# Walrus_Main.net
KiCad netlist of a schematic drawn in Altium Designer
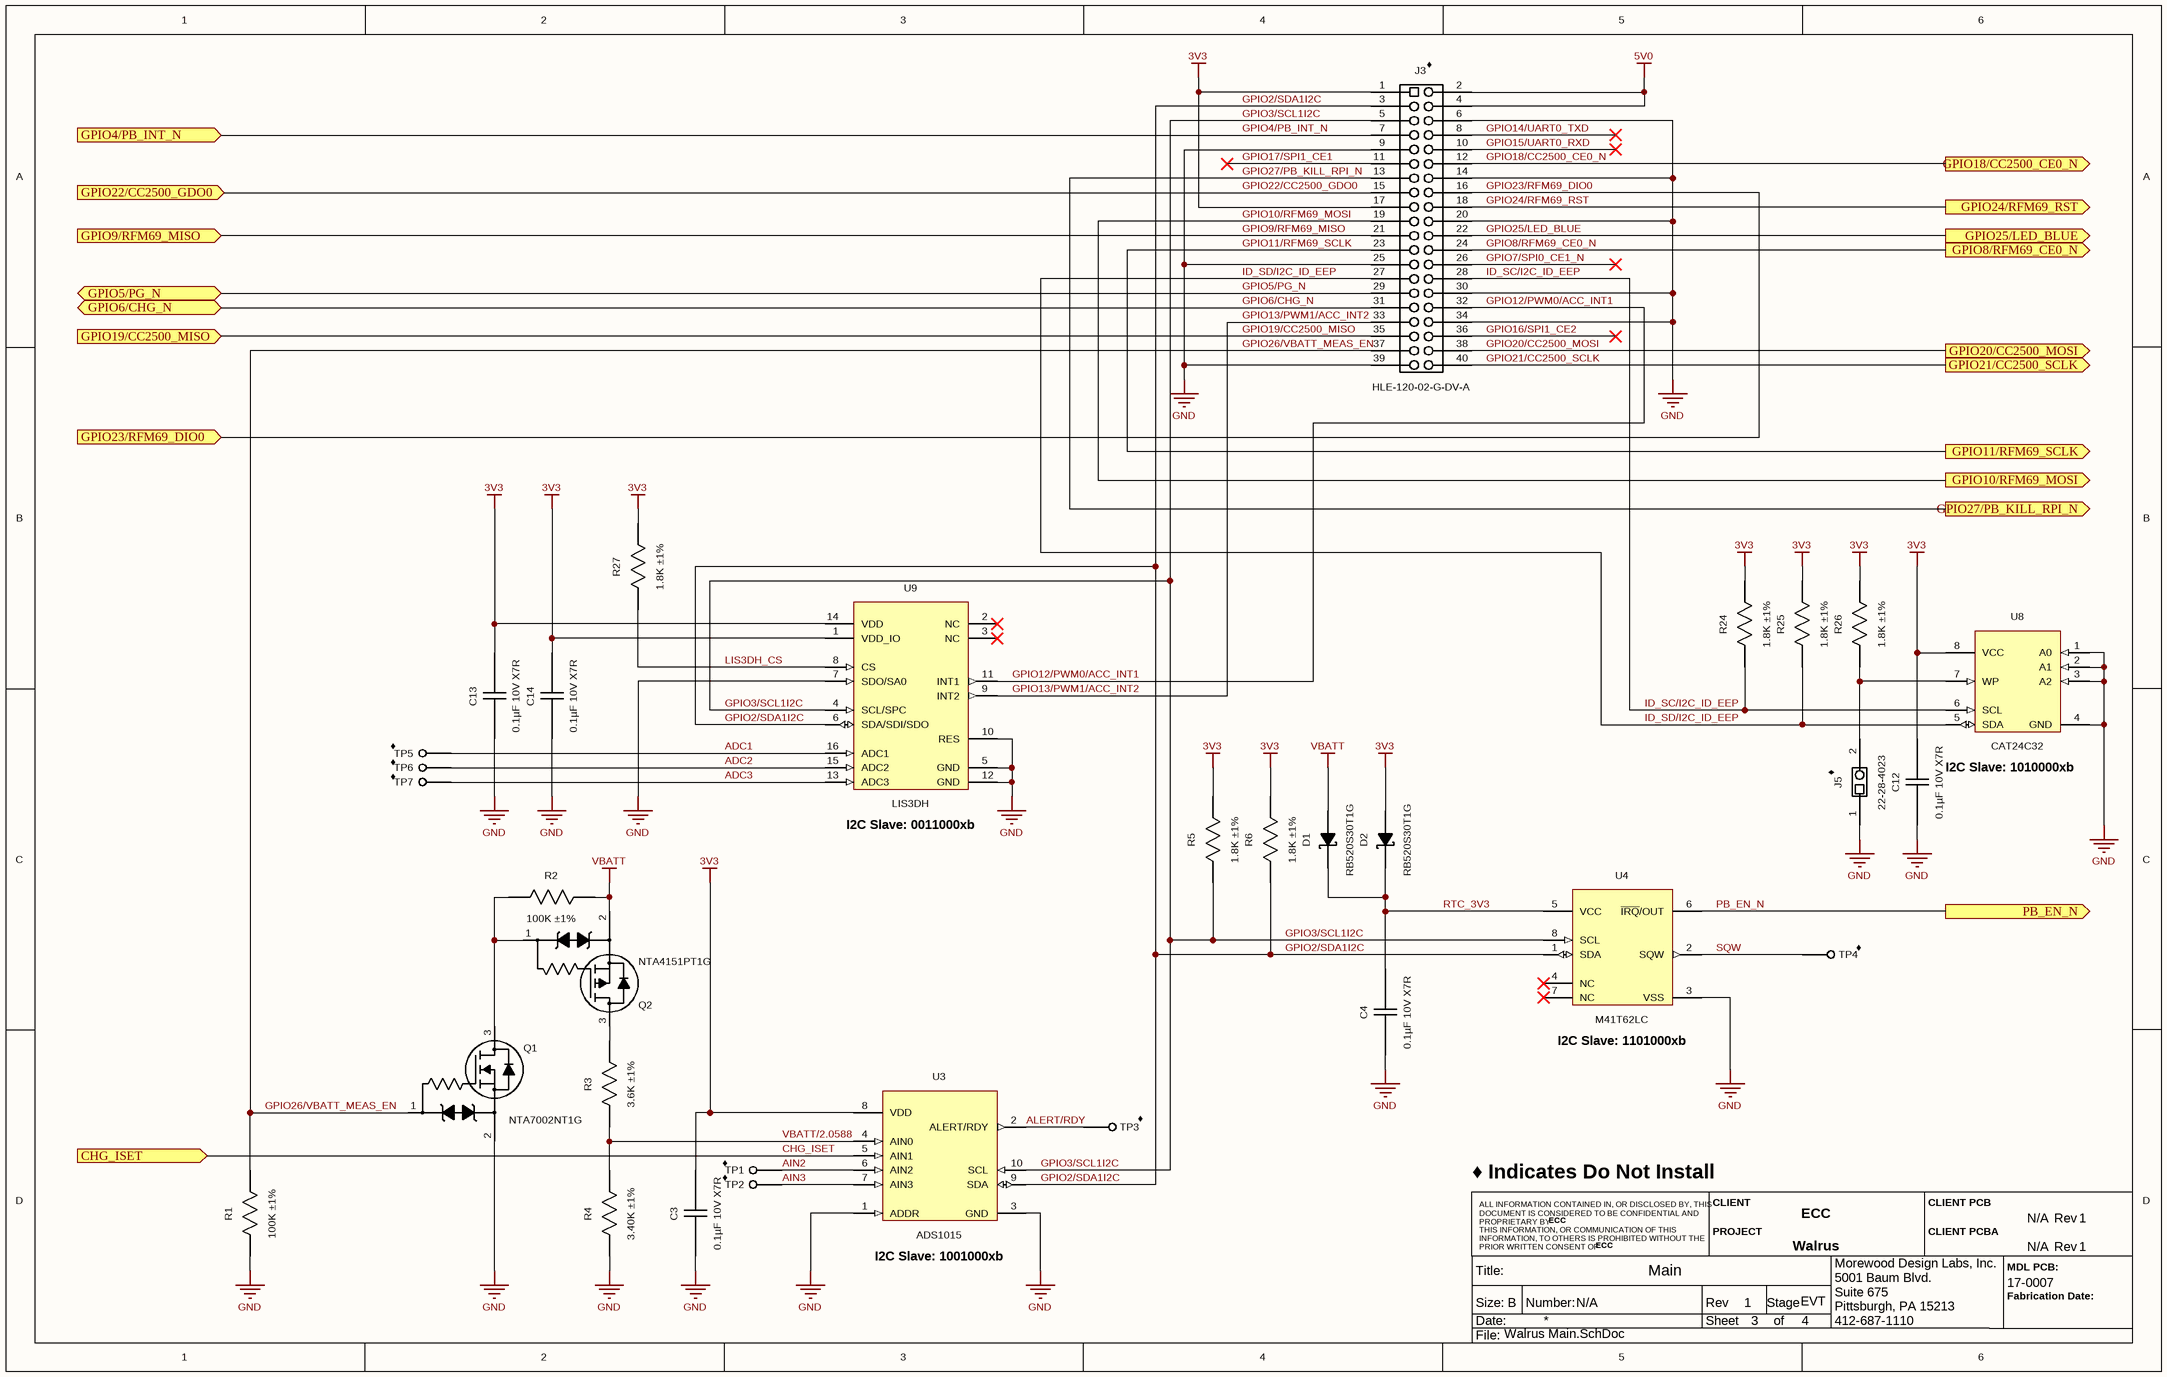
[diagram p0: Walrus Main.SchDoc]

(export (version "E")
  (design (tool "Eeschema 10.0.6"))
  (components
    (comp (ref "C3")
      (value "0.1µF 10V X7R")
      (footprint "CAPC1005X60L(0402_FLEXTRONICS)")
      (description "Ceramic Chip Capacitor")
      (fields
        (field (name "MDLPARTNUMBER") "CAP_000208")
        (field (name "TOLERANCE") "±10%")
        (field (name "CREATOR") "R. Casciola")
      )
      (libsource (lib "Morewood Labs") (part "Capacitor 1"))
    )
    (comp (ref "C4")
      (value "0.1µF 10V X7R")
      (footprint "CAPC1005X60L(0402_FLEXTRONICS)")
      (description "Ceramic Chip Capacitor")
      (fields
        (field (name "MDLPARTNUMBER") "CAP_000208")
        (field (name "TOLERANCE") "±10%")
        (field (name "CREATOR") "R. Casciola")
      )
      (libsource (lib "Morewood Labs") (part "Capacitor 1"))
    )
    (comp (ref "C12")
      (value "0.1µF 10V X7R")
      (footprint "CAPC1005X60L(0402_FLEXTRONICS)")
      (description "Ceramic Chip Capacitor")
      (fields
        (field (name "MDLPARTNUMBER") "CAP_000208")
        (field (name "TOLERANCE") "±10%")
        (field (name "CREATOR") "R. Casciola")
      )
      (libsource (lib "Morewood Labs") (part "Capacitor 1"))
    )
    (comp (ref "C13")
      (value "0.1µF 10V X7R")
      (footprint "CAPC1005X60L(0402_FLEXTRONICS)")
      (description "Ceramic Chip Capacitor")
      (fields
        (field (name "MDLPARTNUMBER") "CAP_000208")
        (field (name "TOLERANCE") "±10%")
        (field (name "CREATOR") "R. Casciola")
      )
      (libsource (lib "Morewood Labs") (part "Capacitor 1"))
    )
    (comp (ref "C14")
      (value "0.1µF 10V X7R")
      (footprint "CAPC1005X60L(0402_FLEXTRONICS)")
      (description "Ceramic Chip Capacitor")
      (fields
        (field (name "MDLPARTNUMBER") "CAP_000208")
        (field (name "TOLERANCE") "±10%")
        (field (name "CREATOR") "R. Casciola")
      )
      (libsource (lib "Morewood Labs") (part "Capacitor 1"))
    )
    (comp (ref "D1")
      (value "RB520S30T1G")
      (footprint "SODFL1608X70L(SOD-523)")
      (description "Schottky Barrier Diode")
      (fields (field (name "MDLPARTNUMBER") "DIOD_000001") (field (name "CREATOR") "R. Casciola"))
      (libsource (lib "Morewood Labs") (part "Diode 3"))
    )
    (comp (ref "D2")
      (value "RB520S30T1G")
      (footprint "SODFL1608X70L(SOD-523)")
      (description "Schottky Barrier Diode")
      (fields (field (name "MDLPARTNUMBER") "DIOD_000001") (field (name "CREATOR") "R. Casciola"))
      (libsource (lib "Morewood Labs") (part "Diode 3"))
    )
    (comp (ref "J3")
      (value "HLE-120-02-G-DV-A")
      (footprint "SAMTEC_HLE-120-02-G-DV-A")
      (description "0.100\" Tiger Beam™ Cost-effective Single Beam Socket Strip")
      (fields
        (field (name "MDLPARTNUMBER") "CONN_000192")
        (field (name "DNI") "♦")
        (field (name "CREATOR") "R. Casciola")
      )
      (libsource (lib "Morewood Labs") (part "FSKT2X20_EVEN_ODD"))
    )
    (comp (ref "J5")
      (value "22-28-4023")
      (footprint "MOLEX_22-28-4023")
      (description "KK 100 HEADER ASSY FLAT VERTICAL BREAKAWAY, 1X2")
      (fields
        (field (name "MDLPARTNUMBER") "CONN_000017")
        (field (name "MFG2PARTNUMBER") "TSW-102-07-T-S")
        (field (name "DNI") "♦")
        (field (name "CREATOR") "R. Casciola")
        (field (name "MODIFER") "R. Casciola")
      )
      (libsource (lib "Morewood Labs") (part "JUMPER_2"))
    )
    (comp (ref "Q1")
      (value "NTA7002NT1G")
      (footprint "SOT50P160X90-3L(SOT416, SC75)")
      (description "Small Signal MOSFET")
      (fields
        (field (name "MDLPARTNUMBER") "TRAN_000002")
        (field (name "CREATOR") "R. Casciola")
        (field (name "MODIFER") "R. Casciola")
      )
      (libsource (lib "Morewood Labs") (part "MOSFET 2"))
    )
    (comp (ref "Q2")
      (value "NTA4151PT1G")
      (footprint "SOT50P160X90-3L(SOT416, SC75)")
      (description "Small Signal MOSFET")
      (fields (field (name "MDLPARTNUMBER") "TRAN_000001") (field (name "CREATOR") "R. Casciola"))
      (libsource (lib "Morewood Labs") (part "MOSFET 1"))
    )
    (comp (ref "R1")
      (value "100K ±1%")
      (footprint "RESC1005X40L(0402)")
      (description "Chip Resistor, Thick Film")
      (fields
        (field (name "MDLPARTNUMBER") "RES_000067")
        (field (name "TOLERANCE") "±1%")
        (field (name "CREATOR") "R. Casciola")
      )
      (libsource (lib "Morewood Labs") (part "Resistor 1"))
    )
    (comp (ref "R2")
      (value "100K ±1%")
      (footprint "RESC1005X40L(0402)")
      (description "Chip Resistor, Thick Film")
      (fields
        (field (name "MDLPARTNUMBER") "RES_000067")
        (field (name "TOLERANCE") "±1%")
        (field (name "CREATOR") "R. Casciola")
      )
      (libsource (lib "Morewood Labs") (part "Resistor 1"))
    )
    (comp (ref "R3")
      (value "3.6K ±1%")
      (footprint "RESC1005X40L(0402)")
      (description "Chip Resistor, Thick Film")
      (fields
        (field (name "MDLPARTNUMBER") "RES_000296")
        (field (name "TOLERANCE") "±1%")
        (field (name "CREATOR") "R. Casciola")
      )
      (libsource (lib "Morewood Labs") (part "Resistor 1"))
    )
    (comp (ref "R4")
      (value "3.40K ±1%")
      (footprint "RESC1005X40L(0402)")
      (description "Chip Resistor, Thick Film")
      (fields
        (field (name "MDLPARTNUMBER") "RES_000253")
        (field (name "TOLERANCE") "±1%")
        (field (name "CREATOR") "R. Casciola")
      )
      (libsource (lib "Morewood Labs") (part "Resistor 1"))
    )
    (comp (ref "R5")
      (value "1.8K ±1%")
      (footprint "RESC1005X40L(0402)")
      (description "Chip Resistor, Thick Film")
      (fields
        (field (name "MDLPARTNUMBER") "RES_000288")
        (field (name "TOLERANCE") "±1%")
        (field (name "CREATOR") "R. Casciola")
      )
      (libsource (lib "Morewood Labs") (part "Resistor 1"))
    )
    (comp (ref "R6")
      (value "1.8K ±1%")
      (footprint "RESC1005X40L(0402)")
      (description "Chip Resistor, Thick Film")
      (fields
        (field (name "MDLPARTNUMBER") "RES_000288")
        (field (name "TOLERANCE") "±1%")
        (field (name "CREATOR") "R. Casciola")
      )
      (libsource (lib "Morewood Labs") (part "Resistor 1"))
    )
    (comp (ref "R24")
      (value "1.8K ±1%")
      (footprint "RESC1005X40L(0402)")
      (description "Chip Resistor, Thick Film")
      (fields
        (field (name "MDLPARTNUMBER") "RES_000288")
        (field (name "TOLERANCE") "±1%")
        (field (name "CREATOR") "R. Casciola")
      )
      (libsource (lib "Morewood Labs") (part "Resistor 1"))
    )
    (comp (ref "R25")
      (value "1.8K ±1%")
      (footprint "RESC1005X40L(0402)")
      (description "Chip Resistor, Thick Film")
      (fields
        (field (name "MDLPARTNUMBER") "RES_000288")
        (field (name "TOLERANCE") "±1%")
        (field (name "CREATOR") "R. Casciola")
      )
      (libsource (lib "Morewood Labs") (part "Resistor 1"))
    )
    (comp (ref "R26")
      (value "1.8K ±1%")
      (footprint "RESC1005X40L(0402)")
      (description "Chip Resistor, Thick Film")
      (fields
        (field (name "MDLPARTNUMBER") "RES_000288")
        (field (name "TOLERANCE") "±1%")
        (field (name "CREATOR") "R. Casciola")
      )
      (libsource (lib "Morewood Labs") (part "Resistor 1"))
    )
    (comp (ref "R27")
      (value "1.8K ±1%")
      (footprint "RESC1005X40L(0402)")
      (description "Chip Resistor, Thick Film")
      (fields
        (field (name "MDLPARTNUMBER") "RES_000288")
        (field (name "TOLERANCE") "±1%")
        (field (name "CREATOR") "R. Casciola")
      )
      (libsource (lib "Morewood Labs") (part "Resistor 1"))
    )
    (comp (ref "TP1")
      (value "Test Point, Through Hole, 1.0mm Pad, 0.5mm Hole")
      (footprint "TP100P50D")
      (description "Test Point")
      (fields
        (field (name "MDLPARTNUMBER") "TP_000015")
        (field (name "DNI") "♦")
        (field (name "CREATOR") "R. Casciola")
      )
      (libsource (lib "Morewood Labs") (part "Test Point 2"))
    )
    (comp (ref "TP2")
      (value "Test Point, Through Hole, 1.0mm Pad, 0.5mm Hole")
      (footprint "TP100P50D")
      (description "Test Point")
      (fields
        (field (name "MDLPARTNUMBER") "TP_000015")
        (field (name "DNI") "♦")
        (field (name "CREATOR") "R. Casciola")
      )
      (libsource (lib "Morewood Labs") (part "Test Point 2"))
    )
    (comp (ref "TP3")
      (value "Test Point, Through Hole, 1.0mm Pad, 0.5mm Hole")
      (footprint "TP100P50D")
      (description "Test Point")
      (fields
        (field (name "MDLPARTNUMBER") "TP_000015")
        (field (name "DNI") "♦")
        (field (name "CREATOR") "R. Casciola")
      )
      (libsource (lib "Morewood Labs") (part "Test Point 2"))
    )
    (comp (ref "TP4")
      (value "Test Point, Through Hole, 1.0mm Pad, 0.5mm Hole")
      (footprint "TP100P50D")
      (description "Test Point")
      (fields
        (field (name "MDLPARTNUMBER") "TP_000015")
        (field (name "DNI") "♦")
        (field (name "CREATOR") "R. Casciola")
      )
      (libsource (lib "Morewood Labs") (part "Test Point 2"))
    )
    (comp (ref "TP5")
      (value "Test Point, Through Hole, 1.0mm Pad, 0.5mm Hole")
      (footprint "TP100P50D")
      (description "Test Point")
      (fields
        (field (name "MDLPARTNUMBER") "TP_000015")
        (field (name "DNI") "♦")
        (field (name "CREATOR") "R. Casciola")
      )
      (libsource (lib "Morewood Labs") (part "Test Point 2"))
    )
    (comp (ref "TP6")
      (value "Test Point, Through Hole, 1.0mm Pad, 0.5mm Hole")
      (footprint "TP100P50D")
      (description "Test Point")
      (fields
        (field (name "MDLPARTNUMBER") "TP_000015")
        (field (name "DNI") "♦")
        (field (name "CREATOR") "R. Casciola")
      )
      (libsource (lib "Morewood Labs") (part "Test Point 2"))
    )
    (comp (ref "TP7")
      (value "Test Point, Through Hole, 1.0mm Pad, 0.5mm Hole")
      (footprint "TP100P50D")
      (description "Test Point")
      (fields
        (field (name "MDLPARTNUMBER") "TP_000015")
        (field (name "DNI") "♦")
        (field (name "CREATOR") "R. Casciola")
      )
      (libsource (lib "Morewood Labs") (part "Test Point 2"))
    )
    (comp (ref "U3")
      (value "ADS1015")
      (footprint "QFN50P200X150X40-10(RUG_R-PQFP-N10)")
      (fields
        (field (name "MDLPARTNUMBER") "IC_000284")
        (field (name "MFG1PARTNUMBER") "ADS1015IRUGR,ADS1015IRUGT")
        (field (name "CREATOR") "R. Casciola")
      )
      (libsource (lib "Morewood Labs") (part "ADS1015"))
    )
    (comp (ref "U4")
      (value "M41T62LC")
      (footprint "LCC90P320X150X80-8N(M41T62)")
      (description "Low-power serial real-time clock (RTCs) with alarm")
      (fields
        (field (name "MDLPARTNUMBER") "IC_000295")
        (field (name "MFG1PARTNUMBER") "M41T62LC6F")
        (field (name "CREATOR") "R. Casciola")
      )
      (libsource (lib "Morewood Labs") (part "M41T62LC"))
    )
    (comp (ref "U8")
      (value "CAT24C32")
      (footprint "SON50P300X200X55-8L(UDFN-8)")
      (description "32-Kb I2C CMOS Serial EEPROM")
      (fields
        (field (name "MDLPARTNUMBER") "IC_000300")
        (field (name "MFG1PARTNUMBER") "CAT24C32HU4I-GT3")
        (field (name "CREATOR") "R. Casciola")
        (field (name "MODIFER") "R. Casciola")
      )
      (libsource (lib "Morewood Labs") (part "CAT24C32HU4"))
    )
    (comp (ref "U9")
      (value "LIS3DH")
      (footprint "LGA50P300X300X100-16N(LGA16)")
      (description "MEMS digital output motion sensor: ultra low-power high performance 3-axes “nano” accelerometer")
      (fields
        (field (name "MDLPARTNUMBER") "IC_000038")
        (field (name "MFG1PARTNUMBER") "LIS3DHTR")
        (field (name "CREATOR") "R. Casciola")
        (field (name "MODIFER") "R. Casciola")
      )
      (libsource (lib "Morewood Labs") (part "LIS3DH"))
    )
  )
  (nets
    (net (code "1") (name "/ADC1") (class "Default")
      (node (ref "TP5") (pin "1") (pintype "passive"))
      (node (ref "U9") (pin "16") (pinfunction "ADC1_16") (pintype "input"))
    )
    (net (code "2") (name "/ADC2") (class "Default")
      (node (ref "TP6") (pin "1") (pintype "passive"))
      (node (ref "U9") (pin "15") (pinfunction "ADC2_15") (pintype "input"))
    )
    (net (code "3") (name "/ADC3") (class "Default")
      (node (ref "TP7") (pin "1") (pintype "passive"))
      (node (ref "U9") (pin "13") (pinfunction "ADC3_13") (pintype "input"))
    )
    (net (code "4") (name "/AIN2") (class "Default")
      (node (ref "TP1") (pin "1") (pintype "passive"))
      (node (ref "U3") (pin "6") (pinfunction "AIN2_6") (pintype "input"))
    )
    (net (code "5") (name "/AIN3") (class "Default")
      (node (ref "TP2") (pin "1") (pintype "passive"))
      (node (ref "U3") (pin "7") (pinfunction "AIN3_7") (pintype "input"))
    )
    (net (code "6") (name "/ALERT{slash}RDY") (class "Default")
      (node (ref "TP3") (pin "1") (pintype "passive"))
      (node (ref "U3") (pin "2") (pinfunction "ALERT/RDY_2") (pintype "output"))
    )
    (net (code "7") (name "/CHG_ISET") (class "Default")
      (node (ref "U3") (pin "5") (pinfunction "AIN1_5") (pintype "input"))
    )
    (net (code "8") (name "/GPIO2{slash}SDA1I2C") (class "Default")
      (node (ref "J3") (pin "3") (pinfunction "3_3") (pintype "passive"))
      (node (ref "R6") (pin "1") (pinfunction "1_1") (pintype "passive"))
      (node (ref "U3") (pin "9") (pinfunction "SDA_9") (pintype "bidirectional"))
      (node (ref "U4") (pin "1") (pinfunction "SDA_1") (pintype "bidirectional"))
      (node (ref "U9") (pin "6") (pinfunction "SDA/SDI/SDO_6") (pintype "bidirectional"))
    )
    (net (code "9") (name "/GPIO3{slash}SCL1I2C") (class "Default")
      (node (ref "J3") (pin "5") (pinfunction "5_5") (pintype "passive"))
      (node (ref "R5") (pin "1") (pinfunction "1_1") (pintype "passive"))
      (node (ref "U3") (pin "10") (pinfunction "SCL_10") (pintype "input"))
      (node (ref "U4") (pin "8") (pinfunction "SCL_8") (pintype "input"))
      (node (ref "U9") (pin "4") (pinfunction "SCL/SPC_4") (pintype "input"))
    )
    (net (code "10") (name "/GPIO4{slash}PB_INT_N") (class "Default")
      (node (ref "J3") (pin "7") (pinfunction "7_7") (pintype "passive"))
    )
    (net (code "11") (name "/GPIO5{slash}PG_N") (class "Default")
      (node (ref "J3") (pin "29") (pinfunction "29_29") (pintype "passive"))
    )
    (net (code "12") (name "/GPIO6{slash}CHG_N") (class "Default")
      (node (ref "J3") (pin "31") (pinfunction "31_31") (pintype "passive"))
    )
    (net (code "13") (name "/GPIO7{slash}SPI0_CE1_N") (class "Default")
      (node (ref "J3") (pin "26") (pinfunction "26_26") (pintype "passive+no_connect"))
    )
    (net (code "14") (name "/GPIO8{slash}RFM69_CE0_N") (class "Default")
      (node (ref "J3") (pin "24") (pinfunction "24_24") (pintype "passive"))
    )
    (net (code "15") (name "/GPIO9{slash}RFM69_MISO") (class "Default")
      (node (ref "J3") (pin "21") (pinfunction "21_21") (pintype "passive"))
    )
    (net (code "16") (name "/GPIO10{slash}RFM69_MOSI") (class "Default")
      (node (ref "J3") (pin "19") (pinfunction "19_19") (pintype "passive"))
    )
    (net (code "17") (name "/GPIO11{slash}RFM69_SCLK") (class "Default")
      (node (ref "J3") (pin "23") (pinfunction "23_23") (pintype "passive"))
    )
    (net (code "18") (name "/GPIO12{slash}PWM0{slash}ACC_INT1") (class "Default")
      (node (ref "J3") (pin "32") (pinfunction "32_32") (pintype "passive"))
      (node (ref "U9") (pin "11") (pinfunction "INT1_11") (pintype "output"))
    )
    (net (code "19") (name "/GPIO13{slash}PWM1{slash}ACC_INT2") (class "Default")
      (node (ref "J3") (pin "33") (pinfunction "33_33") (pintype "passive"))
      (node (ref "U9") (pin "9") (pinfunction "INT2_9") (pintype "output"))
    )
    (net (code "20") (name "/GPIO14{slash}UART0_TXD") (class "Default")
      (node (ref "J3") (pin "8") (pinfunction "8_8") (pintype "passive+no_connect"))
    )
    (net (code "21") (name "/GPIO15{slash}UART0_RXD") (class "Default")
      (node (ref "J3") (pin "10") (pinfunction "10_10") (pintype "passive+no_connect"))
    )
    (net (code "22") (name "/GPIO16{slash}SPI1_CE2") (class "Default")
      (node (ref "J3") (pin "36") (pinfunction "36_36") (pintype "passive+no_connect"))
    )
    (net (code "23") (name "/GPIO17{slash}SPI1_CE1") (class "Default")
      (node (ref "J3") (pin "11") (pinfunction "11_11") (pintype "passive+no_connect"))
    )
    (net (code "24") (name "/GPIO18{slash}CC2500_CE0_N") (class "Default")
      (node (ref "J3") (pin "12") (pinfunction "12_12") (pintype "passive"))
    )
    (net (code "25") (name "/GPIO19{slash}CC2500_MISO") (class "Default")
      (node (ref "J3") (pin "35") (pinfunction "35_35") (pintype "passive"))
    )
    (net (code "26") (name "/GPIO20{slash}CC2500_MOSI") (class "Default")
      (node (ref "J3") (pin "38") (pinfunction "38_38") (pintype "passive"))
    )
    (net (code "27") (name "/GPIO21{slash}CC2500_SCLK") (class "Default")
      (node (ref "J3") (pin "40") (pinfunction "40_40") (pintype "passive"))
    )
    (net (code "28") (name "/GPIO22{slash}CC2500_GDO0") (class "Default")
      (node (ref "J3") (pin "15") (pinfunction "15_15") (pintype "passive"))
    )
    (net (code "29") (name "/GPIO23{slash}RFM69_DIO0") (class "Default")
      (node (ref "J3") (pin "16") (pinfunction "16_16") (pintype "passive"))
    )
    (net (code "30") (name "/GPIO24{slash}RFM69_RST") (class "Default")
      (node (ref "J3") (pin "18") (pinfunction "18_18") (pintype "passive"))
    )
    (net (code "31") (name "/GPIO25{slash}LED_BLUE") (class "Default")
      (node (ref "J3") (pin "22") (pinfunction "22_22") (pintype "passive"))
    )
    (net (code "32") (name "/GPIO26{slash}VBATT_MEAS_EN") (class "Default")
      (node (ref "J3") (pin "37") (pinfunction "37_37") (pintype "passive"))
      (node (ref "Q1") (pin "1") (pinfunction "G_1") (pintype "passive"))
      (node (ref "R1") (pin "2") (pinfunction "2_2") (pintype "passive"))
    )
    (net (code "33") (name "/GPIO27{slash}PB_KILL_RPI_N") (class "Default")
      (node (ref "J3") (pin "13") (pinfunction "13_13") (pintype "passive"))
    )
    (net (code "34") (name "/ID_SC{slash}I2C_ID_EEP") (class "Default")
      (node (ref "J3") (pin "28") (pinfunction "28_28") (pintype "passive"))
      (node (ref "R24") (pin "1") (pinfunction "1_1") (pintype "passive"))
      (node (ref "U8") (pin "6") (pinfunction "SCL_6") (pintype "input"))
    )
    (net (code "35") (name "/ID_SD{slash}I2C_ID_EEP") (class "Default")
      (node (ref "J3") (pin "27") (pinfunction "27_27") (pintype "passive"))
      (node (ref "R25") (pin "1") (pinfunction "1_1") (pintype "passive"))
      (node (ref "U8") (pin "5") (pinfunction "SDA_5") (pintype "bidirectional"))
    )
    (net (code "36") (name "/LIS3DH_CS") (class "Default")
      (node (ref "R27") (pin "1") (pinfunction "1_1") (pintype "passive"))
      (node (ref "U9") (pin "8") (pinfunction "CS_8") (pintype "input"))
    )
    (net (code "37") (name "/PB_EN_N") (class "Default")
      (node (ref "U4") (pin "6") (pinfunction "~{IRQ}/OUT_6") (pintype "open_collector"))
    )
    (net (code "38") (name "/RTC_3V3") (class "Default")
      (node (ref "C4") (pin "2") (pinfunction "2_2") (pintype "passive"))
      (node (ref "D1") (pin "1") (pinfunction "K_1") (pintype "passive"))
      (node (ref "D2") (pin "1") (pinfunction "K_1") (pintype "passive"))
      (node (ref "U4") (pin "5") (pinfunction "VCC_5") (pintype "power_in"))
    )
    (net (code "39") (name "/SQW") (class "Default")
      (node (ref "TP4") (pin "1") (pintype "passive"))
      (node (ref "U4") (pin "2") (pinfunction "SQW_2") (pintype "output"))
    )
    (net (code "40") (name "/VBATT{slash}2.0588") (class "Default")
      (node (ref "R3") (pin "1") (pinfunction "1_1") (pintype "passive"))
      (node (ref "R4") (pin "2") (pinfunction "2_2") (pintype "passive"))
      (node (ref "U3") (pin "4") (pinfunction "AIN0_4") (pintype "input"))
    )
    (net (code "41") (name "3V3") (class "Default")
      (node (ref "C12") (pin "2") (pinfunction "2_2") (pintype "passive"))
      (node (ref "C13") (pin "2") (pinfunction "2_2") (pintype "passive"))
      (node (ref "C14") (pin "2") (pinfunction "2_2") (pintype "passive"))
      (node (ref "C3") (pin "2") (pinfunction "2_2") (pintype "passive"))
      (node (ref "D2") (pin "2") (pinfunction "A_2") (pintype "passive"))
      (node (ref "J3") (pin "1") (pinfunction "1_1") (pintype "passive"))
      (node (ref "J3") (pin "17") (pinfunction "17_17") (pintype "passive"))
      (node (ref "R24") (pin "2") (pinfunction "2_2") (pintype "passive"))
      (node (ref "R25") (pin "2") (pinfunction "2_2") (pintype "passive"))
      (node (ref "R26") (pin "2") (pinfunction "2_2") (pintype "passive"))
      (node (ref "R27") (pin "2") (pinfunction "2_2") (pintype "passive"))
      (node (ref "R5") (pin "2") (pinfunction "2_2") (pintype "passive"))
      (node (ref "R6") (pin "2") (pinfunction "2_2") (pintype "passive"))
      (node (ref "U3") (pin "8") (pinfunction "VDD_8") (pintype "power_in"))
      (node (ref "U8") (pin "8") (pinfunction "VCC_8") (pintype "power_in"))
      (node (ref "U9") (pin "1") (pinfunction "VDD_IO_1") (pintype "power_in"))
      (node (ref "U9") (pin "14") (pinfunction "VDD_14") (pintype "power_in"))
    )
    (net (code "42") (name "5V0") (class "Default")
      (node (ref "J3") (pin "2") (pinfunction "2_2") (pintype "passive"))
      (node (ref "J3") (pin "4") (pinfunction "4_4") (pintype "passive"))
    )
    (net (code "43") (name "GND") (class "Default")
      (node (ref "C12") (pin "1") (pinfunction "1_1") (pintype "passive"))
      (node (ref "C13") (pin "1") (pinfunction "1_1") (pintype "passive"))
      (node (ref "C14") (pin "1") (pinfunction "1_1") (pintype "passive"))
      (node (ref "C3") (pin "1") (pinfunction "1_1") (pintype "passive"))
      (node (ref "C4") (pin "1") (pinfunction "1_1") (pintype "passive"))
      (node (ref "J3") (pin "14") (pinfunction "14_14") (pintype "passive"))
      (node (ref "J3") (pin "20") (pinfunction "20_20") (pintype "passive"))
      (node (ref "J3") (pin "25") (pinfunction "25_25") (pintype "passive"))
      (node (ref "J3") (pin "30") (pinfunction "30_30") (pintype "passive"))
      (node (ref "J3") (pin "34") (pinfunction "34_34") (pintype "passive"))
      (node (ref "J3") (pin "39") (pinfunction "39_39") (pintype "passive"))
      (node (ref "J3") (pin "6") (pinfunction "6_6") (pintype "passive"))
      (node (ref "J3") (pin "9") (pinfunction "9_9") (pintype "passive"))
      (node (ref "J5") (pin "1") (pinfunction "1_1") (pintype "passive"))
      (node (ref "Q1") (pin "2") (pinfunction "S_2") (pintype "passive"))
      (node (ref "R1") (pin "1") (pinfunction "1_1") (pintype "passive"))
      (node (ref "R4") (pin "1") (pinfunction "1_1") (pintype "passive"))
      (node (ref "U3") (pin "1") (pinfunction "ADDR_1") (pintype "input"))
      (node (ref "U3") (pin "3") (pinfunction "GND_3") (pintype "power_in"))
      (node (ref "U4") (pin "3") (pinfunction "VSS_3") (pintype "power_in"))
      (node (ref "U8") (pin "1") (pinfunction "A0_1") (pintype "input"))
      (node (ref "U8") (pin "2") (pinfunction "A1_2") (pintype "input"))
      (node (ref "U8") (pin "3") (pinfunction "A2_3") (pintype "input"))
      (node (ref "U8") (pin "4") (pinfunction "GND_4") (pintype "power_in"))
      (node (ref "U9") (pin "10") (pinfunction "RES_10") (pintype "passive"))
      (node (ref "U9") (pin "12") (pinfunction "GND_12") (pintype "power_in"))
      (node (ref "U9") (pin "5") (pinfunction "GND_5") (pintype "power_in"))
      (node (ref "U9") (pin "7") (pinfunction "SDO/SA0_7") (pintype "input"))
    )
    (net (code "44") (name "Net-(Q1-D)") (class "Default")
      (node (ref "Q1") (pin "3") (pinfunction "D_3") (pintype "passive"))
      (node (ref "Q2") (pin "1") (pinfunction "G_1") (pintype "passive"))
      (node (ref "R2") (pin "1") (pinfunction "1_1") (pintype "passive"))
    )
    (net (code "45") (name "Net-(Q2-D)") (class "Default")
      (node (ref "Q2") (pin "3") (pinfunction "D_3") (pintype "passive"))
      (node (ref "R3") (pin "2") (pinfunction "2_2") (pintype "passive"))
    )
    (net (code "46") (name "Net-(U8-WP)") (class "Default")
      (node (ref "J5") (pin "2") (pinfunction "2_2") (pintype "passive"))
      (node (ref "R26") (pin "1") (pinfunction "1_1") (pintype "passive"))
      (node (ref "U8") (pin "7") (pinfunction "WP_7") (pintype "input"))
    )
    (net (code "47") (name "VBATT") (class "Default")
      (node (ref "D1") (pin "2") (pinfunction "A_2") (pintype "passive"))
      (node (ref "Q2") (pin "2") (pinfunction "S_2") (pintype "passive"))
      (node (ref "R2") (pin "2") (pinfunction "2_2") (pintype "passive"))
    )
    (net (code "48") (name "unconnected-(U4-NC-Pad4)") (class "Default")
      (node (ref "U4") (pin "4") (pinfunction "NC_4") (pintype "passive+no_connect"))
    )
    (net (code "49") (name "unconnected-(U4-NC-Pad7)") (class "Default")
      (node (ref "U4") (pin "7") (pinfunction "NC_7") (pintype "passive+no_connect"))
    )
    (net (code "50") (name "unconnected-(U9-NC-Pad2)") (class "Default")
      (node (ref "U9") (pin "2") (pinfunction "NC_2") (pintype "passive+no_connect"))
    )
    (net (code "51") (name "unconnected-(U9-NC-Pad3)") (class "Default")
      (node (ref "U9") (pin "3") (pinfunction "NC_3") (pintype "passive+no_connect"))
    )
  )
)
